# esp32-thing.net
KiCad netlist of a schematic drawn in EAGLE
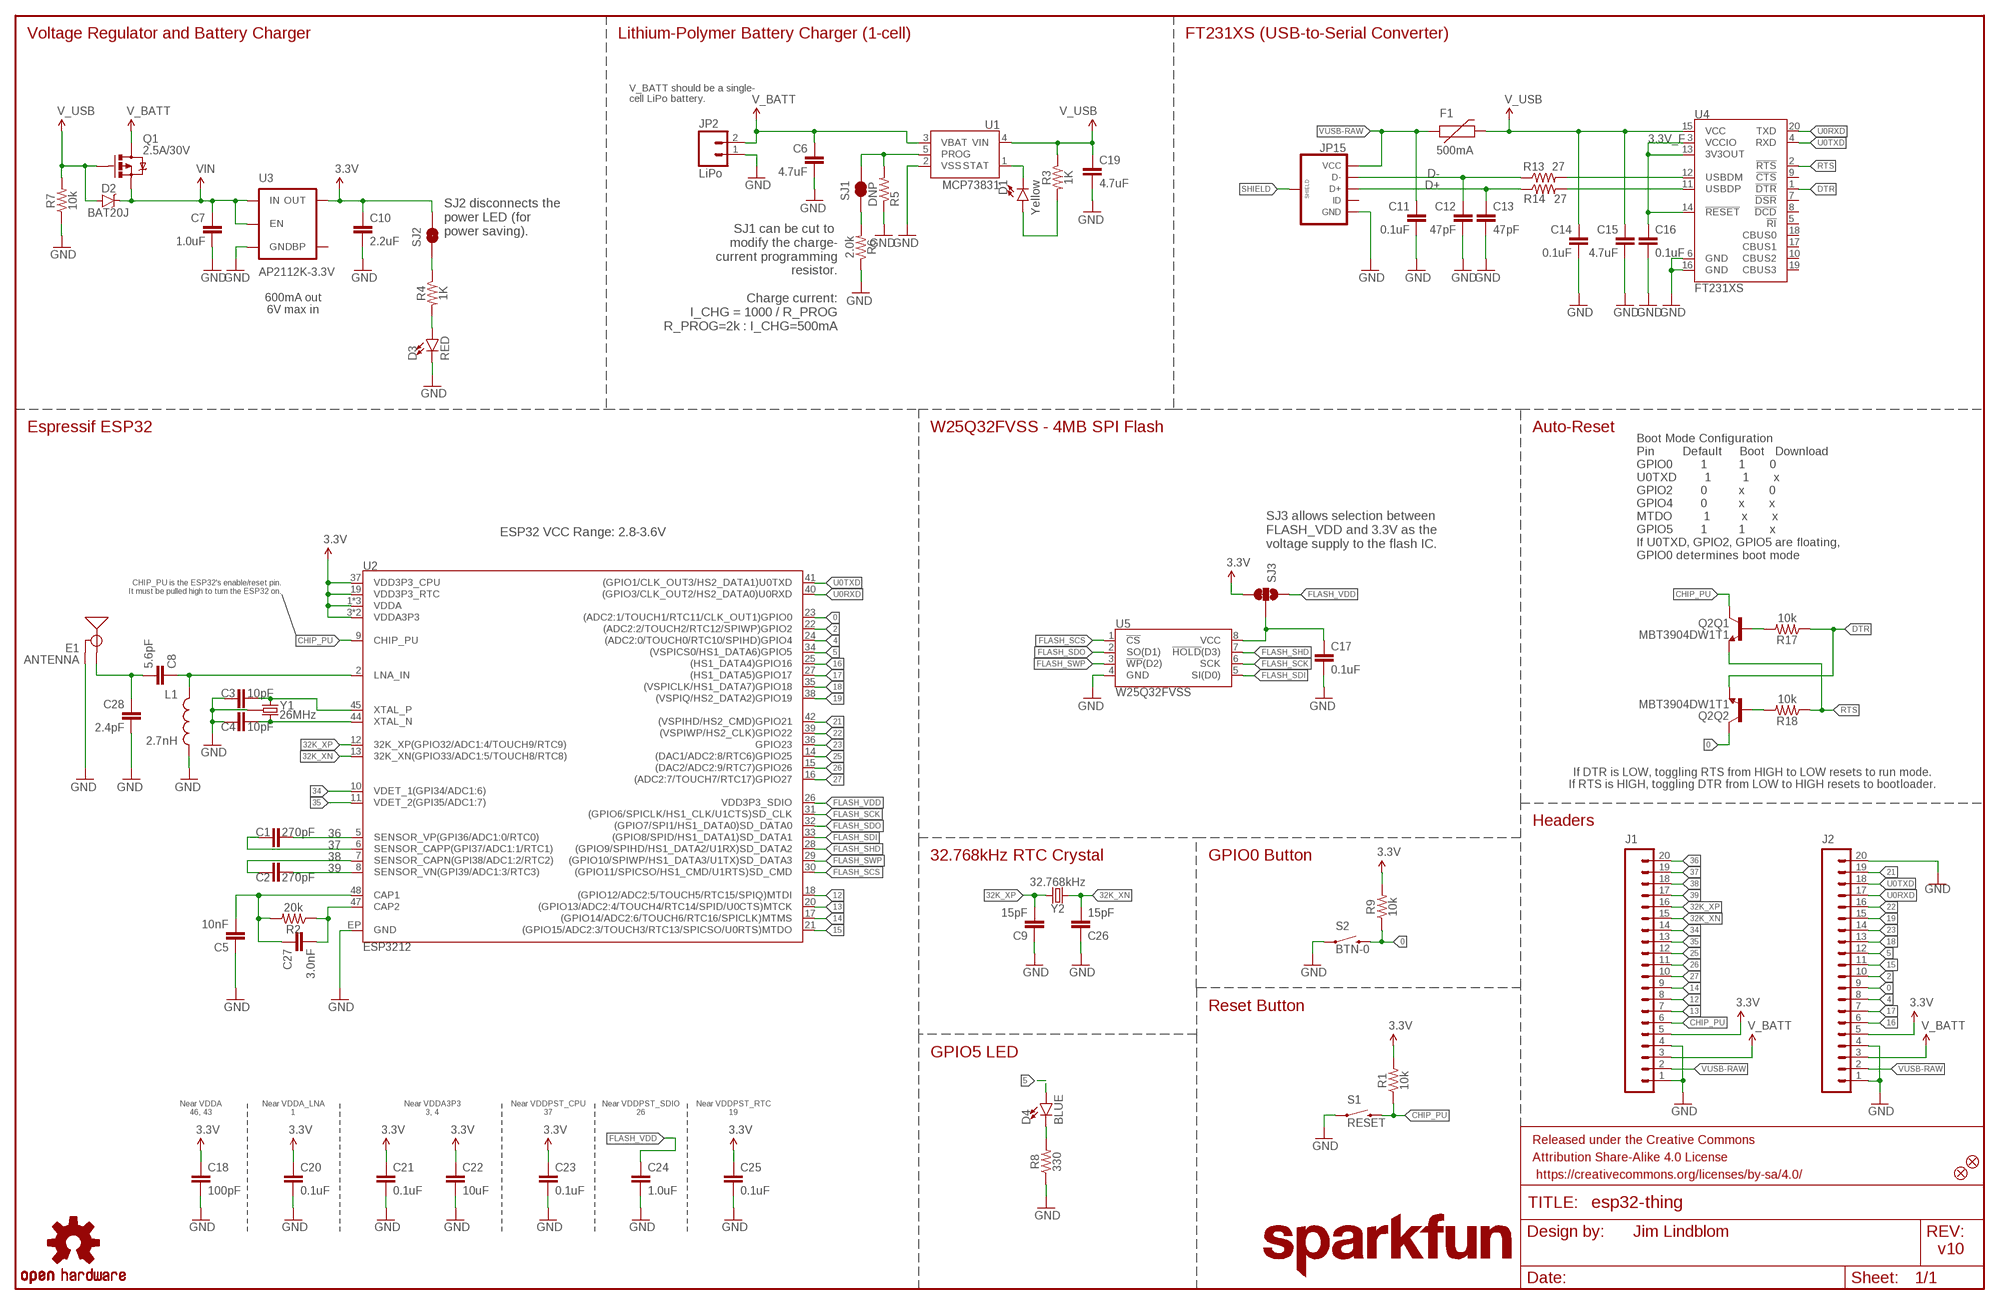
[diagram p0: schematic, sheet 1, part 1 of 2]
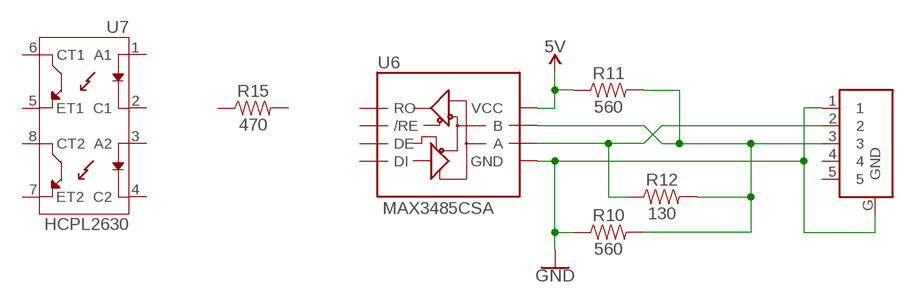
[diagram p1: schematic, sheet 1, part 2 of 2]

(export (version "E")
  (design (tool "Eeschema 10.0.6"))
  (components
    (comp (ref "C1")
      (value "270pF")
      (footprint "eagle-import:0603")
      (libsource (lib "eagle-import") (part "270PF-50V-5%(0603)"))
    )
    (comp (ref "C2")
      (value "270pF")
      (footprint "eagle-import:0603")
      (libsource (lib "eagle-import") (part "270PF-50V-5%(0603)"))
    )
    (comp (ref "C3")
      (value "10pF")
      (footprint "eagle-import:0603")
      (libsource (lib "eagle-import") (part "10PF-0603-50V-5%"))
    )
    (comp (ref "C4")
      (value "10pF")
      (footprint "eagle-import:0603")
      (libsource (lib "eagle-import") (part "10PF-0603-50V-5%"))
    )
    (comp (ref "C5")
      (value "10nF")
      (footprint "eagle-import:0603")
      (libsource (lib "eagle-import") (part "10NF-0603-50V-10%"))
    )
    (comp (ref "C6")
      (value "4.7uF")
      (footprint "eagle-import:0603")
      (libsource (lib "eagle-import") (part "4.7UF0603"))
    )
    (comp (ref "C7")
      (value "1.0uF")
      (footprint "eagle-import:0805")
      (libsource (lib "eagle-import") (part "1.0UF-0805-25V-(+80/-20%)"))
    )
    (comp (ref "C8")
      (value "5.6pF")
      (footprint "eagle-import:0603")
      (libsource (lib "eagle-import") (part "5.6PF-50V-5%(0603)"))
    )
    (comp (ref "C9")
      (value "15pF")
      (footprint "eagle-import:0603")
      (libsource (lib "eagle-import") (part "15PF-0603-50V-5%"))
    )
    (comp (ref "C10")
      (value "2.2uF")
      (footprint "eagle-import:0603")
      (libsource (lib "eagle-import") (part "2.2UF-0603-10V-20%"))
    )
    (comp (ref "C11")
      (value "0.1uF")
      (footprint "eagle-import:0603")
      (libsource (lib "eagle-import") (part "0.1UF-0603-25V-(+80/-20%)"))
    )
    (comp (ref "C12")
      (value "47pF")
      (footprint "eagle-import:0603")
      (libsource (lib "eagle-import") (part "47PF-0603-50V-5%"))
    )
    (comp (ref "C13")
      (value "47pF")
      (footprint "eagle-import:0603")
      (libsource (lib "eagle-import") (part "47PF-0603-50V-5%"))
    )
    (comp (ref "C14")
      (value "0.1uF")
      (footprint "eagle-import:0603")
      (libsource (lib "eagle-import") (part "0.1UF-0603-25V-(+80/-20%)"))
    )
    (comp (ref "C15")
      (value "4.7uF")
      (footprint "eagle-import:0603-CAP")
      (libsource (lib "eagle-import") (part "4.7UF-6.3V-10%(0603)0603"))
    )
    (comp (ref "C16")
      (value "0.1uF")
      (footprint "eagle-import:0603")
      (libsource (lib "eagle-import") (part "0.1UF-0603-25V-(+80/-20%)"))
    )
    (comp (ref "C17")
      (value "0.1uF")
      (footprint "eagle-import:0603")
      (libsource (lib "eagle-import") (part "0.1UF-0603-25V-(+80/-20%)"))
    )
    (comp (ref "C18")
      (value "100pF")
      (footprint "eagle-import:0603")
      (libsource (lib "eagle-import") (part "100PF-0603-50V-5%"))
    )
    (comp (ref "C19")
      (value "4.7uF")
      (footprint "eagle-import:0603")
      (libsource (lib "eagle-import") (part "4.7UF0603"))
    )
    (comp (ref "C20")
      (value "0.1uF")
      (footprint "eagle-import:0603")
      (libsource (lib "eagle-import") (part "0.1UF-0603-25V-(+80/-20%)"))
    )
    (comp (ref "C21")
      (value "0.1uF")
      (footprint "eagle-import:0603")
      (libsource (lib "eagle-import") (part "0.1UF-0603-25V-(+80/-20%)"))
    )
    (comp (ref "C22")
      (value "10uF")
      (footprint "eagle-import:0603")
      (libsource (lib "eagle-import") (part "10UF-0603-6.3V-20%"))
    )
    (comp (ref "C23")
      (value "0.1uF")
      (footprint "eagle-import:0603")
      (libsource (lib "eagle-import") (part "0.1UF-0603-25V-(+80/-20%)"))
    )
    (comp (ref "C24")
      (value "1.0uF")
      (footprint "eagle-import:0603")
      (libsource (lib "eagle-import") (part "1.0UF-0603-16V-10%"))
    )
    (comp (ref "C25")
      (value "0.1uF")
      (footprint "eagle-import:0603")
      (libsource (lib "eagle-import") (part "0.1UF-0603-25V-(+80/-20%)"))
    )
    (comp (ref "C26")
      (value "15pF")
      (footprint "eagle-import:0603")
      (libsource (lib "eagle-import") (part "15PF-0603-50V-5%"))
    )
    (comp (ref "C27")
      (value "3.0nF")
      (footprint "eagle-import:0603")
      (libsource (lib "eagle-import") (part "3.0NF-0603-50V-5%"))
    )
    (comp (ref "C28")
      (value "2.4pF")
      (footprint "eagle-import:0603")
      (libsource (lib "eagle-import") (part "2.4PF-0603-50V-5%"))
    )
    (comp (ref "D1")
      (value "Yellow")
      (footprint "eagle-import:LED-0603")
      (libsource (lib "eagle-import") (part "LED-YELLOW0603"))
    )
    (comp (ref "D2")
      (value "BAT20J")
      (footprint "eagle-import:SOD-323")
      (libsource (lib "eagle-import") (part "DIODE-SCHOTTKY-BAT20J"))
    )
    (comp (ref "D3")
      (value "RED")
      (footprint "eagle-import:LED-0603")
      (libsource (lib "eagle-import") (part "LED-RED0603"))
    )
    (comp (ref "D4")
      (value "BLUE")
      (footprint "eagle-import:LED-0603")
      (libsource (lib "eagle-import") (part "LED-BLUE0603"))
    )
    (comp (ref "E1")
      (value "ANTENNA")
      (footprint "eagle-import:TRACE_ANTENNA_2.4GHZ_25.7MM_TUNED")
      (libsource (lib "eagle-import") (part "ANTENNATRACE-TUNED"))
    )
    (comp (ref "F1")
      (value "500mA")
      (footprint "eagle-import:PTC-1206")
      (libsource (lib "eagle-import") (part "PTCSMD"))
    )
    (comp (ref "FD1")
      (value "FIDUCIALUFIDUCIAL")
      (footprint "eagle-import:MICRO-FIDUCIAL")
      (libsource (lib "eagle-import") (part "FIDUCIALUFIDUCIAL"))
    )
    (comp (ref "FD2")
      (value "FIDUCIALUFIDUCIAL")
      (footprint "eagle-import:MICRO-FIDUCIAL")
      (libsource (lib "eagle-import") (part "FIDUCIALUFIDUCIAL"))
    )
    (comp (ref "FRAME1")
      (value "FRAME-LEDGER")
      (footprint "eagle-import:CREATIVE_COMMONS")
      (libsource (lib "eagle-import") (part "FRAME-LEDGER"))
    )
    (comp (ref "J1")
      (value "M20NOSILK")
      (footprint "eagle-import:1X20_NOSILK")
      (libsource (lib "eagle-import") (part "M20NOSILK"))
    )
    (comp (ref "J2")
      (value "M20NOSILK")
      (footprint "eagle-import:1X20_NOSILK")
      (libsource (lib "eagle-import") (part "M20NOSILK"))
    )
    (comp (ref "JP2")
      (value "LiPo")
      (footprint "eagle-import:JST-2-PTH")
      (libsource (lib "eagle-import") (part "M02JST-PTH-2"))
    )
    (comp (ref "JP15")
      (value "USB_MICROB_PLUGCONN-11752")
      (footprint "eagle-import:USB-B-MICRO-SMD_V03")
      (libsource (lib "eagle-import") (part "USB_MICROB_PLUGCONN-11752"))
    )
    (comp (ref "L1")
      (value "2.7nH")
      (footprint "eagle-import:0603")
      (libsource (lib "eagle-import") (part "INDUCTOR0603"))
    )
    (comp (ref "LOGO1")
      (value "SFE_LOGO_NAME.2_INCH")
      (footprint "eagle-import:SFE_LOGO_NAME_.2")
      (libsource (lib "eagle-import") (part "SFE_LOGO_NAME.2_INCH"))
    )
    (comp (ref "LOGO2")
      (value "OSHW-LOGOMINI")
      (footprint "eagle-import:OSHW-LOGO-MINI")
      (libsource (lib "eagle-import") (part "OSHW-LOGOMINI"))
    )
    (comp (ref "LOGO3")
      (value "SFE_LOGO_NAME.2_INCH")
      (footprint "eagle-import:SFE_LOGO_NAME_.2")
      (libsource (lib "eagle-import") (part "SFE_LOGO_NAME.2_INCH"))
    )
    (comp (ref "Q1")
      (value "2.5A/30V")
      (footprint "eagle-import:SOT23-3")
      (libsource (lib "eagle-import") (part "MOSFET-PCHANNELDMG2307L"))
    )
    (comp (ref "Q2")
      (value "MBT3904DW1T1")
      (footprint "eagle-import:SC70-6")
      (libsource (lib "eagle-import") (part "MBT3904DW1T1"))
    )
    (comp (ref "R1")
      (value "10k")
      (footprint "eagle-import:0603")
      (libsource (lib "eagle-import") (part "10KOHM-1/10W-1%(0603)0603"))
    )
    (comp (ref "R2")
      (value "20k")
      (footprint "eagle-import:0603")
      (libsource (lib "eagle-import") (part "20KOHM-0603-1/10W-1%"))
    )
    (comp (ref "R3")
      (value "1K")
      (footprint "eagle-import:0603")
      (libsource (lib "eagle-import") (part "1KOHM-1/10W-1%(0603)"))
    )
    (comp (ref "R4")
      (value "1K")
      (footprint "eagle-import:0603")
      (libsource (lib "eagle-import") (part "1KOHM-1/10W-1%(0603)"))
    )
    (comp (ref "R5")
      (value "DNP")
      (footprint "eagle-import:1_6W-RES")
      (libsource (lib "eagle-import") (part "RESISTORPTH-1/6W"))
    )
    (comp (ref "R6")
      (value "2.0k")
      (footprint "eagle-import:0603")
      (libsource (lib "eagle-import") (part "2.0KOHM1/10W5%(0603)"))
    )
    (comp (ref "R7")
      (value "10k")
      (footprint "eagle-import:0603")
      (libsource (lib "eagle-import") (part "10KOHM-0603-1/10W-1%"))
    )
    (comp (ref "R8")
      (value "330")
      (footprint "eagle-import:0603")
      (libsource (lib "eagle-import") (part "330OHM1/10W1%(0603)"))
    )
    (comp (ref "R9")
      (value "10k")
      (footprint "eagle-import:0603")
      (libsource (lib "eagle-import") (part "10KOHM-1/10W-1%(0603)0603"))
    )
    (comp (ref "R10")
      (value "560")
      (footprint "eagle-import:0402")
      (libsource (lib "eagle-import") (part "560OHM_0402_1%"))
    )
    (comp (ref "R11")
      (value "560")
      (footprint "eagle-import:0402")
      (libsource (lib "eagle-import") (part "560OHM_0402_1%"))
    )
    (comp (ref "R12")
      (value "130")
      (footprint "eagle-import:0603")
      (libsource (lib "eagle-import") (part "RESISTOR0603"))
    )
    (comp (ref "R13")
      (value "27")
      (footprint "eagle-import:0603")
      (libsource (lib "eagle-import") (part "27OHM1/10W1%(0603)0603-RES"))
    )
    (comp (ref "R14")
      (value "27")
      (footprint "eagle-import:0603")
      (libsource (lib "eagle-import") (part "27OHM1/10W1%(0603)0603-RES"))
    )
    (comp (ref "R15")
      (value "470")
      (footprint "eagle-import:0603")
      (libsource (lib "eagle-import") (part "470OHM-0603-1/10W-1%"))
    )
    (comp (ref "R17")
      (value "10k")
      (footprint "eagle-import:0603")
      (libsource (lib "eagle-import") (part "10KOHM-0603-1/10W-1%"))
    )
    (comp (ref "R18")
      (value "10k")
      (footprint "eagle-import:0603")
      (libsource (lib "eagle-import") (part "10KOHM-0603-1/10W-1%"))
    )
    (comp (ref "S1")
      (value "RESET")
      (footprint "eagle-import:TACTILE_SWITCH_SMD_4.6X2.8MM")
      (libsource (lib "eagle-import") (part "SWITCH-MOMENTARY-2SMD-4.6X2.8MM"))
    )
    (comp (ref "S2")
      (value "BTN-0")
      (footprint "eagle-import:TACTILE_SWITCH_SMD_4.6X2.8MM")
      (libsource (lib "eagle-import") (part "SWITCH-MOMENTARY-2SMD-4.6X2.8MM"))
    )
    (comp (ref "SJ1")
      (value "JUMPER-PAD-2-NC_BY_TRACE")
      (footprint "eagle-import:PAD-JUMPER-2-NC_BY_TRACE_YES_SILK")
      (libsource (lib "eagle-import") (part "JUMPER-PAD-2-NC_BY_TRACE"))
    )
    (comp (ref "SJ2")
      (value "JUMPER-PAD-2-NC_BY_TRACE")
      (footprint "eagle-import:PAD-JUMPER-2-NC_BY_TRACE_YES_SILK")
      (libsource (lib "eagle-import") (part "JUMPER-PAD-2-NC_BY_TRACE"))
    )
    (comp (ref "SJ3")
      (value "JUMPER-PAD-3-2OF3_NC_BY_TRACE_SMALL")
      (footprint "eagle-import:PAD-JUMPER-3-2OF3_NC_BY_TRACE_YES_SILK_FULL_BOX")
      (libsource (lib "eagle-import") (part "JUMPER-PAD-3-2OF3_NC_BY_TRACE_SMALL"))
    )
    (comp (ref "U$1")
      (value "XLR-5")
      (footprint "eagle-import:XLR-5")
      (libsource (lib "eagle-import") (part "XLR-5"))
    )
    (comp (ref "U1")
      (value "MCP73831")
      (footprint "eagle-import:SOT23-5")
      (libsource (lib "eagle-import") (part "MCP73831"))
    )
    (comp (ref "U2")
      (value "ESP3212")
      (footprint "eagle-import:QFN48-0.4MM")
      (libsource (lib "eagle-import") (part "ESP3212"))
    )
    (comp (ref "U3")
      (value "AP2112K-3.3V")
      (footprint "eagle-import:SOT23-5")
      (libsource (lib "eagle-import") (part "V_REG_LDOSMD"))
    )
    (comp (ref "U4")
      (value "FT231XS")
      (footprint "eagle-import:SSOP20_L")
      (libsource (lib "eagle-import") (part "FT231XS"))
    )
    (comp (ref "U5")
      (value "W25Q32FVSS")
      (footprint "eagle-import:SOIC-8")
      (libsource (lib "eagle-import") (part "W25Q32FVSS"))
    )
    (comp (ref "U6")
      (value "MAX3485CSA")
      (footprint "eagle-import:SO08")
      (libsource (lib "eagle-import") (part "RS485SOIC"))
    )
    (comp (ref "U7")
      (value "HCPL2630")
      (footprint "eagle-import:SO08")
      (libsource (lib "eagle-import") (part "ILD213T-IDL213T"))
    )
    (comp (ref "Y1")
      (value "26MHz")
      (footprint "eagle-import:CRYSTAL-SMD-3.2X2.5")
      (libsource (lib "eagle-import") (part "CRYSTAL-GROUNDED3.2X2.5"))
    )
    (comp (ref "Y2")
      (value "32.768kHz")
      (footprint "eagle-import:CRYSTAL-SMD-3.2X1.5MM")
      (libsource (lib "eagle-import") (part "CRYSTAL-32.768KHZSMD-3.2X1.5"))
    )
  )
  (nets
    (net (code "1") (name "/3.3V_F") (class "Default")
      (node (ref "C16") (pin "1") (pinfunction "1_1") (pintype "passive"))
      (node (ref "U4") (pin "13") (pinfunction "3V3OUT_13") (pintype "bidirectional"))
      (node (ref "U4") (pin "14") (pinfunction "~{RESET}_14") (pintype "bidirectional"))
      (node (ref "U4") (pin "3") (pinfunction "VCCIO_3") (pintype "bidirectional"))
    )
    (net (code "2") (name "/D+") (class "Default")
      (node (ref "C13") (pin "1") (pinfunction "1_1") (pintype "passive"))
      (node (ref "JP15") (pin "D+") (pinfunction "D+_D+") (pintype "bidirectional"))
      (node (ref "R14") (pin "1") (pinfunction "1_1") (pintype "passive"))
    )
    (net (code "3") (name "/D-") (class "Default")
      (node (ref "C12") (pin "1") (pinfunction "1_1") (pintype "passive"))
      (node (ref "JP15") (pin "D-") (pinfunction "D-_D-") (pintype "bidirectional"))
      (node (ref "R13") (pin "1") (pinfunction "1_1") (pintype "passive"))
    )
    (net (code "4") (name "0") (class "Default")
      (node (ref "J2") (pin "9") (pinfunction "9_9") (pintype "passive"))
      (node (ref "Q2") (pin "6") (pinfunction "C_6") (pintype "passive"))
      (node (ref "R9") (pin "1") (pinfunction "1_1") (pintype "passive"))
      (node (ref "S2") (pin "3") (pinfunction "2_3") (pintype "passive"))
      (node (ref "S2") (pin "4") (pinfunction "2_4") (pintype "passive"))
      (node (ref "U2") (pin "23") (pinfunction "(ADC2:1/TOUCH1/RTC11/CLK_OUT1)GPIO0_23") (pintype "bidirectional"))
    )
    (net (code "5") (name "2") (class "Default")
      (node (ref "J2") (pin "10") (pinfunction "10_10") (pintype "passive"))
      (node (ref "U2") (pin "22") (pinfunction "(ADC2:2/TOUCH2/RTC12/SPIWP)GPIO2_22") (pintype "bidirectional"))
    )
    (net (code "6") (name "3.3V") (class "Default")
      (node (ref "C10") (pin "1") (pinfunction "1_1") (pintype "passive"))
      (node (ref "C18") (pin "1") (pinfunction "1_1") (pintype "passive"))
      (node (ref "C20") (pin "1") (pinfunction "1_1") (pintype "passive"))
      (node (ref "C21") (pin "1") (pinfunction "1_1") (pintype "passive"))
      (node (ref "C22") (pin "1") (pinfunction "1_1") (pintype "passive"))
      (node (ref "C23") (pin "1") (pinfunction "1_1") (pintype "passive"))
      (node (ref "C25") (pin "1") (pinfunction "1_1") (pintype "passive"))
      (node (ref "J1") (pin "5") (pinfunction "5_5") (pintype "passive"))
      (node (ref "J2") (pin "5") (pinfunction "5_5") (pintype "passive"))
      (node (ref "R1") (pin "2") (pinfunction "2_2") (pintype "passive"))
      (node (ref "R9") (pin "2") (pinfunction "2_2") (pintype "passive"))
      (node (ref "SJ2") (pin "2") (pinfunction "2_2") (pintype "passive"))
      (node (ref "SJ3") (pin "3") (pinfunction "3_3") (pintype "passive"))
      (node (ref "U2") (pin "1") (pinfunction "VDDA_1") (pintype "bidirectional"))
      (node (ref "U2") (pin "19") (pinfunction "VDD3P3_RTC_19") (pintype "bidirectional"))
      (node (ref "U2") (pin "3") (pinfunction "VDDA3P3_3") (pintype "bidirectional"))
      (node (ref "U2") (pin "37") (pinfunction "VDD3P3_CPU_37") (pintype "bidirectional"))
      (node (ref "U2") (pin "4") (pinfunction "VDDA3P3_4") (pintype "bidirectional"))
      (node (ref "U2") (pin "43") (pinfunction "VDDA_43") (pintype "bidirectional"))
      (node (ref "U2") (pin "46") (pinfunction "VDDA_46") (pintype "bidirectional"))
      (node (ref "U3") (pin "5") (pinfunction "OUT_5") (pintype "passive"))
    )
    (net (code "7") (name "4") (class "Default")
      (node (ref "J2") (pin "8") (pinfunction "8_8") (pintype "passive"))
      (node (ref "U2") (pin "24") (pinfunction "(ADC2:0/TOUCH0/RTC10/SPIHD)GPIO4_24") (pintype "bidirectional"))
    )
    (net (code "8") (name "5") (class "Default")
      (node (ref "D4") (pin "A") (pinfunction "A_A") (pintype "passive"))
      (node (ref "J2") (pin "12") (pinfunction "12_12") (pintype "passive"))
      (node (ref "U2") (pin "34") (pinfunction "(VSPICS0/HS1_DATA6)GPIO5_34") (pintype "bidirectional"))
    )
    (net (code "9") (name "5V") (class "Default")
      (node (ref "R11") (pin "1") (pinfunction "1_1") (pintype "passive"))
      (node (ref "U6") (pin "8") (pinfunction "VCC_8") (pintype "bidirectional"))
    )
    (net (code "10") (name "12") (class "Default")
      (node (ref "J1") (pin "8") (pinfunction "8_8") (pintype "passive"))
      (node (ref "U2") (pin "18") (pinfunction "(GPIO12/ADC2:5/TOUCH5/RTC15/SPIQ)MTDI_18") (pintype "bidirectional"))
    )
    (net (code "11") (name "13") (class "Default")
      (node (ref "J1") (pin "7") (pinfunction "7_7") (pintype "passive"))
      (node (ref "U2") (pin "20") (pinfunction "(GPIO13/ADC2:4/TOUCH4/RTC14/SPID/U0CTS)MTCK_20") (pintype "bidirectional"))
    )
    (net (code "12") (name "14") (class "Default")
      (node (ref "J1") (pin "9") (pinfunction "9_9") (pintype "passive"))
      (node (ref "U2") (pin "17") (pinfunction "(GPIO14/ADC2:6/TOUCH6/RTC16/SPICLK)MTMS_17") (pintype "bidirectional"))
    )
    (net (code "13") (name "15") (class "Default")
      (node (ref "J2") (pin "11") (pinfunction "11_11") (pintype "passive"))
      (node (ref "U2") (pin "21") (pinfunction "(GPIO15/ADC2:3/TOUCH3/RTC13/SPICSO/U0RTS)MTDO_21") (pintype "bidirectional"))
    )
    (net (code "14") (name "16") (class "Default")
      (node (ref "J2") (pin "6") (pinfunction "6_6") (pintype "passive"))
      (node (ref "U2") (pin "25") (pinfunction "(HS1_DATA4)GPIO16_25") (pintype "bidirectional"))
    )
    (net (code "15") (name "17") (class "Default")
      (node (ref "J2") (pin "7") (pinfunction "7_7") (pintype "passive"))
      (node (ref "U2") (pin "27") (pinfunction "(HS1_DATA5)GPIO17_27") (pintype "bidirectional"))
    )
    (net (code "16") (name "18") (class "Default")
      (node (ref "J2") (pin "13") (pinfunction "13_13") (pintype "passive"))
      (node (ref "U2") (pin "35") (pinfunction "(VSPICLK/HS1_DATA7)GPIO18_35") (pintype "bidirectional"))
    )
    (net (code "17") (name "19") (class "Default")
      (node (ref "J2") (pin "15") (pinfunction "15_15") (pintype "passive"))
      (node (ref "U2") (pin "38") (pinfunction "(VSPIQ/HS2_DATA2)GPIO19_38") (pintype "bidirectional"))
    )
    (net (code "18") (name "21") (class "Default")
      (node (ref "J2") (pin "19") (pinfunction "19_19") (pintype "passive"))
      (node (ref "U2") (pin "42") (pinfunction "(VSPIHD/HS2_CMD)GPIO21_42") (pintype "bidirectional"))
    )
    (net (code "19") (name "22") (class "Default")
      (node (ref "J2") (pin "16") (pinfunction "16_16") (pintype "passive"))
      (node (ref "U2") (pin "39") (pinfunction "(VSPIWP/HS2_CLK)GPIO22_39") (pintype "bidirectional"))
    )
    (net (code "20") (name "23") (class "Default")
      (node (ref "J2") (pin "14") (pinfunction "14_14") (pintype "passive"))
      (node (ref "U2") (pin "36") (pinfunction "GPIO23_36") (pintype "bidirectional"))
    )
    (net (code "21") (name "25") (class "Default")
      (node (ref "J1") (pin "12") (pinfunction "12_12") (pintype "passive"))
      (node (ref "U2") (pin "14") (pinfunction "(DAC1/ADC2:8/RTC6)GPIO25_14") (pintype "bidirectional"))
    )
    (net (code "22") (name "26") (class "Default")
      (node (ref "J1") (pin "11") (pinfunction "11_11") (pintype "passive"))
      (node (ref "U2") (pin "15") (pinfunction "(DAC2/ADC2:9/RTC7)GPIO26_15") (pintype "bidirectional"))
    )
    (net (code "23") (name "27") (class "Default")
      (node (ref "J1") (pin "10") (pinfunction "10_10") (pintype "passive"))
      (node (ref "U2") (pin "16") (pinfunction "(ADC2:7/TOUCH7/RTC17)GPIO27_16") (pintype "bidirectional"))
    )
    (net (code "24") (name "32K_XN") (class "Default")
      (node (ref "C26") (pin "2") (pinfunction "2_2") (pintype "passive"))
      (node (ref "J1") (pin "15") (pinfunction "15_15") (pintype "passive"))
      (node (ref "U2") (pin "13") (pinfunction "32K_XN(GPIO33/ADC1:5/TOUCH8/RTC8)_13") (pintype "bidirectional"))
      (node (ref "Y2") (pin "P$2") (pinfunction "2_P$2") (pintype "passive"))
    )
    (net (code "25") (name "32K_XP") (class "Default")
      (node (ref "C9") (pin "2") (pinfunction "2_2") (pintype "passive"))
      (node (ref "J1") (pin "16") (pinfunction "16_16") (pintype "passive"))
      (node (ref "U2") (pin "12") (pinfunction "32K_XP(GPIO32/ADC1:4/TOUCH9/RTC9)_12") (pintype "bidirectional"))
      (node (ref "Y2") (pin "P$1") (pinfunction "1_P$1") (pintype "passive"))
    )
    (net (code "26") (name "34") (class "Default")
      (node (ref "J1") (pin "14") (pinfunction "14_14") (pintype "passive"))
      (node (ref "U2") (pin "10") (pinfunction "VDET_1(GPI34/ADC1:6)_10") (pintype "bidirectional"))
    )
    (net (code "27") (name "35") (class "Default")
      (node (ref "J1") (pin "13") (pinfunction "13_13") (pintype "passive"))
      (node (ref "U2") (pin "11") (pinfunction "VDET_2(GPI35/ADC1:7)_11") (pintype "bidirectional"))
    )
    (net (code "28") (name "36") (class "Default")
      (node (ref "C1") (pin "2") (pinfunction "2_2") (pintype "passive"))
      (node (ref "J1") (pin "20") (pinfunction "20_20") (pintype "passive"))
      (node (ref "U2") (pin "5") (pinfunction "SENSOR_VP(GPI36/ADC1:0/RTC0)_5") (pintype "bidirectional"))
    )
    (net (code "29") (name "37") (class "Default")
      (node (ref "C1") (pin "1") (pinfunction "1_1") (pintype "passive"))
      (node (ref "J1") (pin "19") (pinfunction "19_19") (pintype "passive"))
      (node (ref "U2") (pin "6") (pinfunction "SENSOR_CAPP(GPI37/ADC1:1/RTC1)_6") (pintype "bidirectional"))
    )
    (net (code "30") (name "38") (class "Default")
      (node (ref "C2") (pin "1") (pinfunction "1_1") (pintype "passive"))
      (node (ref "J1") (pin "18") (pinfunction "18_18") (pintype "passive"))
      (node (ref "U2") (pin "7") (pinfunction "SENSOR_CAPN(GPI38/ADC1:2/RTC2)_7") (pintype "bidirectional"))
    )
    (net (code "31") (name "39") (class "Default")
      (node (ref "C2") (pin "2") (pinfunction "2_2") (pintype "passive"))
      (node (ref "J1") (pin "17") (pinfunction "17_17") (pintype "passive"))
      (node (ref "U2") (pin "8") (pinfunction "SENSOR_VN(GPI39/ADC1:3/RTC3)_8") (pintype "bidirectional"))
    )
    (net (code "32") (name "CHIP_PU") (class "Default")
      (node (ref "J1") (pin "6") (pinfunction "6_6") (pintype "passive"))
      (node (ref "Q2") (pin "3") (pinfunction "C_3") (pintype "passive"))
      (node (ref "R1") (pin "1") (pinfunction "1_1") (pintype "passive"))
      (node (ref "S1") (pin "3") (pinfunction "2_3") (pintype "passive"))
      (node (ref "S1") (pin "4") (pinfunction "2_4") (pintype "passive"))
      (node (ref "U2") (pin "9") (pinfunction "CHIP_PU_9") (pintype "bidirectional"))
    )
    (net (code "33") (name "DTR") (class "Default")
      (node (ref "Q2") (pin "1") (pinfunction "E_1") (pintype "passive"))
      (node (ref "R17") (pin "1") (pinfunction "1_1") (pintype "passive"))
      (node (ref "U4") (pin "1") (pinfunction "~{DTR}_1") (pintype "bidirectional"))
    )
    (net (code "34") (name "FLASH_SCK") (class "Default")
      (node (ref "U2") (pin "31") (pinfunction "(GPIO6/SPICLK/HS1_CLK/U1CTS)SD_CLK_31") (pintype "bidirectional"))
      (node (ref "U5") (pin "6") (pinfunction "SCK_6") (pintype "bidirectional"))
    )
    (net (code "35") (name "FLASH_SCS") (class "Default")
      (node (ref "U2") (pin "30") (pinfunction "(GPIO11/SPICSO/HS1_CMD/U1RTS)SD_CMD_30") (pintype "bidirectional"))
      (node (ref "U5") (pin "1") (pinfunction "~{CS}_1") (pintype "bidirectional"))
    )
    (net (code "36") (name "FLASH_SDI") (class "Default")
      (node (ref "U2") (pin "33") (pinfunction "(GPIO8/SPID/HS1_DATA1)SD_DATA1_33") (pintype "bidirectional"))
      (node (ref "U5") (pin "5") (pinfunction "SI(D0)_5") (pintype "bidirectional"))
    )
    (net (code "37") (name "FLASH_SDO") (class "Default")
      (node (ref "U2") (pin "32") (pinfunction "(GPIO7/SPI1/HS1_DATA0)SD_DATA0_32") (pintype "bidirectional"))
      (node (ref "U5") (pin "2") (pinfunction "SO(D1)_2") (pintype "bidirectional"))
    )
    (net (code "38") (name "FLASH_SHD") (class "Default")
      (node (ref "U2") (pin "28") (pinfunction "(GPIO9/SPIHD/HS1_DATA2/U1RX)SD_DATA2_28") (pintype "bidirectional"))
      (node (ref "U5") (pin "7") (pinfunction "~{HOLD}(D3)_7") (pintype "bidirectional"))
    )
    (net (code "39") (name "FLASH_SWP") (class "Default")
      (node (ref "U2") (pin "29") (pinfunction "(GPIO10/SPIWP/HS1_DATA3/U1TX)SD_DATA3_29") (pintype "bidirectional"))
      (node (ref "U5") (pin "3") (pinfunction "~{WP}(D2)_3") (pintype "bidirectional"))
    )
    (net (code "40") (name "FLASH_VDD") (class "Default")
      (node (ref "C24") (pin "1") (pinfunction "1_1") (pintype "passive"))
      (node (ref "SJ3") (pin "1") (pinfunction "1_1") (pintype "passive"))
      (node (ref "U2") (pin "26") (pinfunction "VDD3P3_SDIO_26") (pintype "bidirectional"))
    )
    (net (code "41") (name "GND") (class "Default")
      (node (ref "C10") (pin "2") (pinfunction "2_2") (pintype "passive"))
      (node (ref "C11") (pin "2") (pinfunction "2_2") (pintype "passive"))
      (node (ref "C12") (pin "2") (pinfunction "2_2") (pintype "passive"))
      (node (ref "C13") (pin "2") (pinfunction "2_2") (pintype "passive"))
      (node (ref "C14") (pin "2") (pinfunction "2_2") (pintype "passive"))
      (node (ref "C15") (pin "2") (pinfunction "2_2") (pintype "passive"))
      (node (ref "C16") (pin "2") (pinfunction "2_2") (pintype "passive"))
      (node (ref "C17") (pin "2") (pinfunction "2_2") (pintype "passive"))
      (node (ref "C18") (pin "2") (pinfunction "2_2") (pintype "passive"))
      (node (ref "C19") (pin "2") (pinfunction "2_2") (pintype "passive"))
      (node (ref "C20") (pin "2") (pinfunction "2_2") (pintype "passive"))
      (node (ref "C21") (pin "2") (pinfunction "2_2") (pintype "passive"))
      (node (ref "C22") (pin "2") (pinfunction "2_2") (pintype "passive"))
      (node (ref "C23") (pin "2") (pinfunction "2_2") (pintype "passive"))
      (node (ref "C24") (pin "2") (pinfunction "2_2") (pintype "passive"))
      (node (ref "C25") (pin "2") (pinfunction "2_2") (pintype "passive"))
      (node (ref "C26") (pin "1") (pinfunction "1_1") (pintype "passive"))
      (node (ref "C28") (pin "2") (pinfunction "2_2") (pintype "passive"))
      (node (ref "C3") (pin "1") (pinfunction "1_1") (pintype "passive"))
      (node (ref "C4") (pin "1") (pinfunction "1_1") (pintype "passive"))
      (node (ref "C5") (pin "1") (pinfunction "1_1") (pintype "passive"))
      (node (ref "C6") (pin "2") (pinfunction "2_2") (pintype "passive"))
      (node (ref "C7") (pin "2") (pinfunction "2_2") (pintype "passive"))
      (node (ref "C9") (pin "1") (pinfunction "1_1") (pintype "passive"))
      (node (ref "D3") (pin "C") (pinfunction "C_C") (pintype "passive"))
      (node (ref "E1") (pin "GND") (pinfunction "GND_GND") (pintype "bidirectional"))
      (node (ref "E1") (pin "GND2") (pinfunction "GND_GND2") (pintype "bidirectional"))
      (node (ref "J1") (pin "1") (pinfunction "1_1") (pintype "passive"))
      (node (ref "J1") (pin "4") (pinfunction "4_4") (pintype "passive"))
      (node (ref "J2") (pin "1") (pinfunction "1_1") (pintype "passive"))
      (node (ref "J2") (pin "20") (pinfunction "20_20") (pintype "passive"))
      (node (ref "J2") (pin "4") (pinfunction "4_4") (pintype "passive"))
      (node (ref "JP15") (pin "GND") (pinfunction "GND_GND") (pintype "bidirectional"))
      (node (ref "JP2") (pin "1") (pinfunction "1_1") (pintype "passive"))
      (node (ref "L1") (pin "2") (pinfunction "2_2") (pintype "passive"))
      (node (ref "R10") (pin "1") (pinfunction "1_1") (pintype "passive"))
      (node (ref "R5") (pin "1") (pinfunction "1_1") (pintype "passive"))
      (node (ref "R6") (pin "1") (pinfunction "1_1") (pintype "passive"))
      (node (ref "R7") (pin "1") (pinfunction "1_1") (pintype "passive"))
      (node (ref "R8") (pin "1") (pinfunction "1_1") (pintype "passive"))
      (node (ref "S1") (pin "1") (pinfunction "1_1") (pintype "passive"))
      (node (ref "S1") (pin "2") (pinfunction "1_2") (pintype "passive"))
      (node (ref "S2") (pin "1") (pinfunction "1_1") (pintype "passive"))
      (node (ref "S2") (pin "2") (pinfunction "1_2") (pintype "passive"))
      (node (ref "U$1") (pin "1") (pinfunction "1_1") (pintype "bidirectional"))
      (node (ref "U$1") (pin "G") (pinfunction "GND_G") (pintype "bidirectional"))
      (node (ref "U1") (pin "2") (pinfunction "VSS_2") (pintype "power_in"))
      (node (ref "U2") (pin "EP") (pinfunction "GND_EP") (pintype "bidirectional"))
      (node (ref "U3") (pin "2") (pinfunction "GND_2") (pintype "input"))
      (node (ref "U4") (pin "16") (pinfunction "GND_16") (pintype "bidirectional"))
      (node (ref "U4") (pin "6") (pinfunction "GND_6") (pintype "bidirectional"))
      (node (ref "U5") (pin "4") (pinfunction "GND_4") (pintype "bidirectional"))
      (node (ref "U6") (pin "5") (pinfunction "GND_5") (pintype "bidirectional"))
      (node (ref "Y1") (pin "2") (pinfunction "GND_2") (pintype "passive"))
      (node (ref "Y1") (pin "4") (pinfunction "GND_4") (pintype "passive"))
    )
    (net (code "42") (name "Net-(D1-PadA)") (class "Default")
      (node (ref "D1") (pin "A") (pinfunction "A_A") (pintype "passive"))
      (node (ref "R3") (pin "2") (pinfunction "2_2") (pintype "passive"))
    )
    (net (code "43") (name "Net-(D3-PadA)") (class "Default")
      (node (ref "D3") (pin "A") (pinfunction "A_A") (pintype "passive"))
      (node (ref "R4") (pin "2") (pinfunction "2_2") (pintype "passive"))
    )
    (net (code "44") (name "Net-(D4-PadC)") (class "Default")
      (node (ref "D4") (pin "C") (pinfunction "C_C") (pintype "passive"))
      (node (ref "R8") (pin "2") (pinfunction "2_2") (pintype "passive"))
    )
    (net (code "45") (name "Net-(E1-SIGNAL)") (class "Default")
      (node (ref "C28") (pin "1") (pinfunction "1_1") (pintype "passive"))
      (node (ref "C8") (pin "2") (pinfunction "2_2") (pintype "passive"))
      (node (ref "E1") (pin "ANT") (pinfunction "SIGNAL_ANT") (pintype "bidirectional"))
    )
    (net (code "46") (name "Net-(Q2A-B)") (class "Default")
      (node (ref "Q2") (pin "5") (pinfunction "B_5") (pintype "passive"))
      (node (ref "R17") (pin "2") (pinfunction "2_2") (pintype "passive"))
    )
    (net (code "47") (name "Net-(Q2B-B)") (class "Default")
      (node (ref "Q2") (pin "2") (pinfunction "B_2") (pintype "passive"))
      (node (ref "R18") (pin "2") (pinfunction "2_2") (pintype "passive"))
    )
    (net (code "48") (name "Net-(R4-Pad1)") (class "Default")
      (node (ref "R4") (pin "1") (pinfunction "1_1") (pintype "passive"))
      (node (ref "SJ2") (pin "1") (pinfunction "1_1") (pintype "passive"))
    )
    (net (code "49") (name "Net-(R6-Pad2)") (class "Default")
      (node (ref "R6") (pin "2") (pinfunction "2_2") (pintype "passive"))
      (node (ref "SJ1") (pin "1") (pinfunction "1_1") (pintype "passive"))
    )
    (net (code "50") (name "Net-(U1-PROG)") (class "Default")
      (node (ref "R5") (pin "2") (pinfunction "2_2") (pintype "passive"))
      (node (ref "SJ1") (pin "2") (pinfunction "2_2") (pintype "passive"))
      (node (ref "U1") (pin "5") (pinfunction "PROG_5") (pintype "input"))
    )
    (net (code "51") (name "Net-(U1-STAT)") (class "Default")
      (node (ref "D1") (pin "C") (pinfunction "C_C") (pintype "passive"))
      (node (ref "U1") (pin "1") (pinfunction "STAT_1") (pintype "output"))
    )
    (net (code "52") (name "Net-(U2-CAP1)") (class "Default")
      (node (ref "C27") (pin "1") (pinfunction "1_1") (pintype "passive"))
      (node (ref "C5") (pin "2") (pinfunction "2_2") (pintype "passive"))
      (node (ref "R2") (pin "2") (pinfunction "2_2") (pintype "passive"))
      (node (ref "U2") (pin "48") (pinfunction "CAP1_48") (pintype "bidirectional"))
    )
    (net (code "53") (name "Net-(U2-CAP2)") (class "Default")
      (node (ref "C27") (pin "2") (pinfunction "2_2") (pintype "passive"))
      (node (ref "R2") (pin "1") (pinfunction "1_1") (pintype "passive"))
      (node (ref "U2") (pin "47") (pinfunction "CAP2_47") (pintype "bidirectional"))
    )
    (net (code "54") (name "Net-(U2-LNA_IN)") (class "Default")
      (node (ref "C8") (pin "1") (pinfunction "1_1") (pintype "passive"))
      (node (ref "L1") (pin "1") (pinfunction "1_1") (pintype "passive"))
      (node (ref "U2") (pin "2") (pinfunction "LNA_IN_2") (pintype "bidirectional"))
    )
    (net (code "55") (name "Net-(U2-XTAL_N)") (class "Default")
      (node (ref "C4") (pin "2") (pinfunction "2_2") (pintype "passive"))
      (node (ref "U2") (pin "44") (pinfunction "XTAL_N_44") (pintype "bidirectional"))
      (node (ref "Y1") (pin "3") (pinfunction "2_3") (pintype "passive"))
    )
    (net (code "56") (name "Net-(U2-XTAL_P)") (class "Default")
      (node (ref "C3") (pin "2") (pinfunction "2_2") (pintype "passive"))
      (node (ref "U2") (pin "45") (pinfunction "XTAL_P_45") (pintype "bidirectional"))
      (node (ref "Y1") (pin "1") (pinfunction "1_1") (pintype "passive"))
    )
    (net (code "57") (name "Net-(U4-USBDM)") (class "Default")
      (node (ref "R13") (pin "2") (pinfunction "2_2") (pintype "passive"))
      (node (ref "U4") (pin "12") (pinfunction "USBDM_12") (pintype "bidirectional"))
    )
    (net (code "58") (name "Net-(U4-USBDP)") (class "Default")
      (node (ref "R14") (pin "2") (pinfunction "2_2") (pintype "passive"))
      (node (ref "U4") (pin "11") (pinfunction "USBDP_11") (pintype "bidirectional"))
    )
    (net (code "59") (name "Net-(U5-VCC)") (class "Default")
      (node (ref "C17") (pin "1") (pinfunction "1_1") (pintype "passive"))
      (node (ref "SJ3") (pin "2") (pinfunction "2_2") (pintype "passive"))
      (node (ref "U5") (pin "8") (pinfunction "VCC_8") (pintype "bidirectional"))
    )
    (net (code "60") (name "Net-(U6-A)") (class "Default")
      (node (ref "R12") (pin "1") (pinfunction "1_1") (pintype "passive"))
      (node (ref "U$1") (pin "2") (pinfunction "2_2") (pintype "bidirectional"))
      (node (ref "U6") (pin "6") (pinfunction "A_6") (pintype "bidirectional"))
    )
    (net (code "61") (name "Net-(U6-B)") (class "Default")
      (node (ref "R10") (pin "2") (pinfunction "2_2") (pintype "passive"))
      (node (ref "R11") (pin "2") (pinfunction "2_2") (pintype "passive"))
      (node (ref "R12") (pin "2") (pinfunction "2_2") (pintype "passive"))
      (node (ref "U$1") (pin "3") (pinfunction "3_3") (pintype "bidirectional"))
      (node (ref "U6") (pin "7") (pinfunction "B_7") (pintype "bidirectional"))
    )
    (net (code "62") (name "RTS") (class "Default")
      (node (ref "Q2") (pin "4") (pinfunction "E_4") (pintype "passive"))
      (node (ref "R18") (pin "1") (pinfunction "1_1") (pintype "passive"))
      (node (ref "U4") (pin "2") (pinfunction "~{RTS}_2") (pintype "bidirectional"))
    )
    (net (code "63") (name "SHIELD") (class "Default")
      (node (ref "JP15") (pin "SHIELD1") (pinfunction "SHIELD_SHIELD1") (pintype "bidirectional"))
      (node (ref "JP15") (pin "SHIELD2") (pinfunction "SHIELD_SHIELD2") (pintype "bidirectional"))
      (node (ref "JP15") (pin "SHIELD3") (pinfunction "SHIELD_SHIELD3") (pintype "bidirectional"))
    )
    (net (code "64") (name "U0RXD") (class "Default")
      (node (ref "J2") (pin "17") (pinfunction "17_17") (pintype "passive"))
      (node (ref "U2") (pin "40") (pinfunction "(GPIO3/CLK_OUT2/HS2_DATA0)U0RXD_40") (pintype "bidirectional"))
      (node (ref "U4") (pin "20") (pinfunction "TXD_20") (pintype "bidirectional"))
    )
    (net (code "65") (name "U0TXD") (class "Default")
      (node (ref "J2") (pin "18") (pinfunction "18_18") (pintype "passive"))
      (node (ref "U2") (pin "41") (pinfunction "(GPIO1/CLK_OUT3/HS2_DATA1)U0TXD_41") (pintype "bidirectional"))
      (node (ref "U4") (pin "4") (pinfunction "RXD_4") (pintype "bidirectional"))
    )
    (net (code "66") (name "VIN") (class "Default")
      (node (ref "C7") (pin "1") (pinfunction "1_1") (pintype "passive"))
      (node (ref "D2") (pin "C") (pinfunction "C_C") (pintype "passive"))
      (node (ref "Q1") (pin "2") (pinfunction "S_2") (pintype "passive"))
      (node (ref "U3") (pin "1") (pinfunction "IN_1") (pintype "input"))
      (node (ref "U3") (pin "3") (pinfunction "EN_3") (pintype "input"))
    )
    (net (code "67") (name "VUSB-RAW") (class "Default")
      (node (ref "C11") (pin "1") (pinfunction "1_1") (pintype "passive"))
      (node (ref "F1") (pin "1") (pinfunction "1_1") (pintype "bidirectional"))
      (node (ref "J1") (pin "2") (pinfunction "2_2") (pintype "passive"))
      (node (ref "J2") (pin "2") (pinfunction "2_2") (pintype "passive"))
      (node (ref "JP15") (pin "VBUS") (pinfunction "VCC_VBUS") (pintype "bidirectional"))
    )
    (net (code "68") (name "V_BATT") (class "Default")
      (node (ref "C6") (pin "1") (pinfunction "1_1") (pintype "passive"))
      (node (ref "J1") (pin "3") (pinfunction "3_3") (pintype "passive"))
      (node (ref "J2") (pin "3") (pinfunction "3_3") (pintype "passive"))
      (node (ref "JP2") (pin "2") (pinfunction "2_2") (pintype "passive"))
      (node (ref "Q1") (pin "3") (pinfunction "D_3") (pintype "passive"))
      (node (ref "U1") (pin "3") (pinfunction "VBAT_3") (pintype "power_in"))
    )
    (net (code "69") (name "V_USB") (class "Default")
      (node (ref "C14") (pin "1") (pinfunction "1_1") (pintype "passive"))
      (node (ref "C15") (pin "1") (pinfunction "1_1") (pintype "passive"))
      (node (ref "C19") (pin "1") (pinfunction "1_1") (pintype "passive"))
      (node (ref "D2") (pin "A") (pinfunction "A_A") (pintype "passive"))
      (node (ref "F1") (pin "2") (pinfunction "2_2") (pintype "bidirectional"))
      (node (ref "Q1") (pin "1") (pinfunction "G_1") (pintype "passive"))
      (node (ref "R3") (pin "1") (pinfunction "1_1") (pintype "passive"))
      (node (ref "R7") (pin "2") (pinfunction "2_2") (pintype "passive"))
      (node (ref "U1") (pin "4") (pinfunction "VIN_4") (pintype "power_in"))
      (node (ref "U4") (pin "15") (pinfunction "VCC_15") (pintype "bidirectional"))
    )
    (net (code "70") (name "unconnected-(JP15-PadID)") (class "Default")
      (node (ref "JP15") (pin "ID") (pinfunction "ID_ID") (pintype "bidirectional"))
    )
    (net (code "71") (name "unconnected-(R15-Pad1)") (class "Default")
      (node (ref "R15") (pin "1") (pinfunction "1_1") (pintype "passive"))
    )
    (net (code "72") (name "unconnected-(R15-Pad2)") (class "Default")
      (node (ref "R15") (pin "2") (pinfunction "2_2") (pintype "passive"))
    )
    (net (code "73") (name "unconnected-(U$1-Pad4)") (class "Default")
      (node (ref "U$1") (pin "4") (pinfunction "4_4") (pintype "bidirectional"))
    )
    (net (code "74") (name "unconnected-(U$1-Pad5)") (class "Default")
      (node (ref "U$1") (pin "5") (pinfunction "5_5") (pintype "bidirectional"))
    )
    (net (code "75") (name "unconnected-(U3-BP-Pad4)") (class "Default")
      (node (ref "U3") (pin "4") (pinfunction "BP_4") (pintype "input"))
    )
    (net (code "76") (name "unconnected-(U4-CBUS0-Pad18)") (class "Default")
      (node (ref "U4") (pin "18") (pinfunction "CBUS0_18") (pintype "bidirectional"))
    )
    (net (code "77") (name "unconnected-(U4-CBUS1-Pad17)") (class "Default")
      (node (ref "U4") (pin "17") (pinfunction "CBUS1_17") (pintype "bidirectional"))
    )
    (net (code "78") (name "unconnected-(U4-CBUS2-Pad10)") (class "Default")
      (node (ref "U4") (pin "10") (pinfunction "CBUS2_10") (pintype "bidirectional"))
    )
    (net (code "79") (name "unconnected-(U4-CBUS3-Pad19)") (class "Default")
      (node (ref "U4") (pin "19") (pinfunction "CBUS3_19") (pintype "bidirectional"))
    )
    (net (code "80") (name "unconnected-(U4-~{CTS}-Pad9)") (class "Default")
      (node (ref "U4") (pin "9") (pinfunction "~{CTS}_9") (pintype "bidirectional"))
    )
    (net (code "81") (name "unconnected-(U4-~{DCD}-Pad8)") (class "Default")
      (node (ref "U4") (pin "8") (pinfunction "~{DCD}_8") (pintype "bidirectional"))
    )
    (net (code "82") (name "unconnected-(U4-~{DSR}-Pad7)") (class "Default")
      (node (ref "U4") (pin "7") (pinfunction "~{DSR}_7") (pintype "bidirectional"))
    )
    (net (code "83") (name "unconnected-(U4-~{RI}-Pad5)") (class "Default")
      (node (ref "U4") (pin "5") (pinfunction "~{RI}_5") (pintype "bidirectional"))
    )
    (net (code "84") (name "unconnected-(U6-DE-Pad3)") (class "Default")
      (node (ref "U6") (pin "3") (pinfunction "DE_3") (pintype "bidirectional"))
    )
    (net (code "85") (name "unconnected-(U6-DI-Pad4)") (class "Default")
      (node (ref "U6") (pin "4") (pinfunction "DI_4") (pintype "bidirectional"))
    )
    (net (code "86") (name "unconnected-(U6-RO-Pad1)") (class "Default")
      (node (ref "U6") (pin "1") (pinfunction "RO_1") (pintype "bidirectional"))
    )
    (net (code "87") (name "unconnected-(U6-{slash}RE-Pad2)") (class "Default")
      (node (ref "U6") (pin "2") (pinfunction "/RE_2") (pintype "bidirectional"))
    )
    (net (code "88") (name "unconnected-(U7-A1-Pad1)") (class "Default")
      (node (ref "U7") (pin "1") (pinfunction "A1_1") (pintype "bidirectional"))
    )
    (net (code "89") (name "unconnected-(U7-A2-Pad3)") (class "Default")
      (node (ref "U7") (pin "3") (pinfunction "A2_3") (pintype "bidirectional"))
    )
    (net (code "90") (name "unconnected-(U7-C1-Pad2)") (class "Default")
      (node (ref "U7") (pin "2") (pinfunction "C1_2") (pintype "bidirectional"))
    )
    (net (code "91") (name "unconnected-(U7-C2-Pad4)") (class "Default")
      (node (ref "U7") (pin "4") (pinfunction "C2_4") (pintype "bidirectional"))
    )
    (net (code "92") (name "unconnected-(U7-CT1-Pad6)") (class "Default")
      (node (ref "U7") (pin "6") (pinfunction "CT1_6") (pintype "bidirectional"))
    )
    (net (code "93") (name "unconnected-(U7-CT2-Pad8)") (class "Default")
      (node (ref "U7") (pin "8") (pinfunction "CT2_8") (pintype "bidirectional"))
    )
    (net (code "94") (name "unconnected-(U7-ET1-Pad5)") (class "Default")
      (node (ref "U7") (pin "5") (pinfunction "ET1_5") (pintype "bidirectional"))
    )
    (net (code "95") (name "unconnected-(U7-ET2-Pad7)") (class "Default")
      (node (ref "U7") (pin "7") (pinfunction "ET2_7") (pintype "bidirectional"))
    )
  )
)
